# main.net
KiCad netlist of a schematic drawn in EAGLE
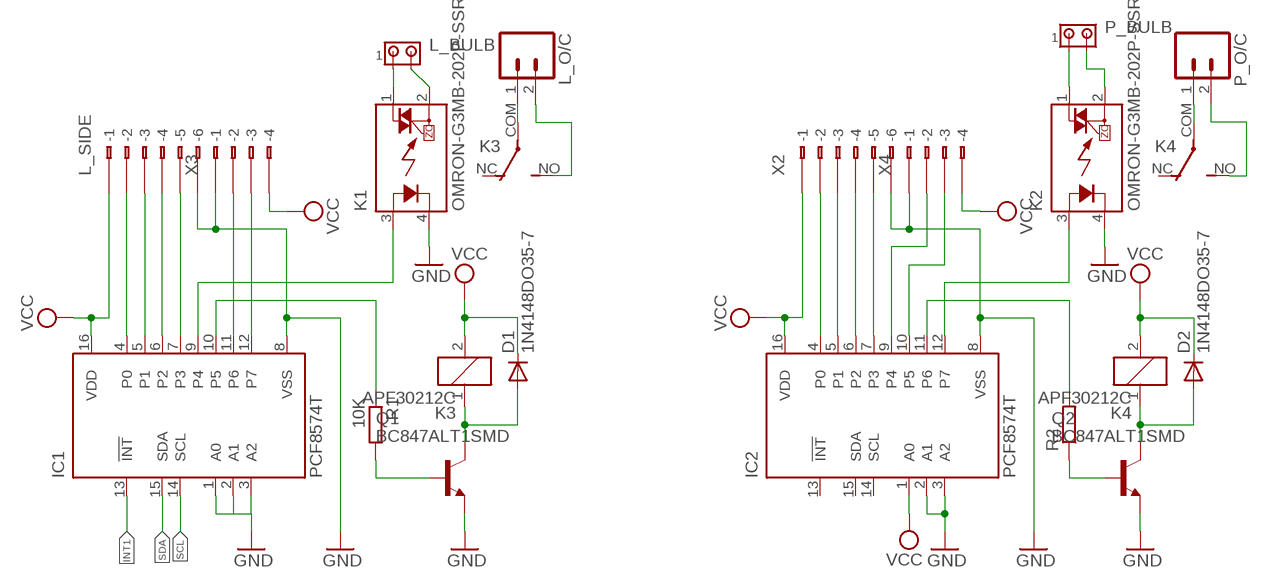
[diagram p0: schematic, sheet 1]

(export (version "E")
  (design (tool "Eeschema 10.0.6"))
  (components
    (comp (ref "D1")
      (value "1N4148DO35-7")
      (footprint "eagle-import:DO35-7")
      (libsource (lib "eagle-import") (part "1N4148DO35-7"))
    )
    (comp (ref "D2")
      (value "1N4148DO35-7")
      (footprint "eagle-import:DO35-7")
      (libsource (lib "eagle-import") (part "1N4148DO35-7"))
    )
    (comp (ref "IC1")
      (value "PCF8574T")
      (footprint "eagle-import:SO16W")
      (fields (field (name "MPN") "PCF8574T/3,512"))
      (libsource (lib "eagle-import") (part "PCF8574T"))
    )
    (comp (ref "IC2")
      (value "PCF8574T")
      (footprint "eagle-import:SO16W")
      (fields (field (name "MPN") "PCF8574T/3,512"))
      (libsource (lib "eagle-import") (part "PCF8574T"))
    )
    (comp (ref "K1")
      (value "OMRON-G3MB-202P-SSR")
      (footprint "eagle-import:OMRON-G3MB-202P-SSR")
      (libsource (lib "eagle-import") (part "OMRON-G3MB-202P-SSR"))
    )
    (comp (ref "K2")
      (value "OMRON-G3MB-202P-SSR")
      (footprint "eagle-import:OMRON-G3MB-202P-SSR")
      (libsource (lib "eagle-import") (part "OMRON-G3MB-202P-SSR"))
    )
    (comp (ref "K3")
      (value "APF30212C")
      (footprint "eagle-import:APF30212C")
      (libsource (lib "eagle-import") (part "APF30212C"))
    )
    (comp (ref "K4")
      (value "APF30212C")
      (footprint "eagle-import:APF30212C")
      (libsource (lib "eagle-import") (part "APF30212C"))
    )
    (comp (ref "L_BULB")
      (value "MTA02-156")
      (footprint "eagle-import:1X2MTA")
      (libsource (lib "eagle-import") (part "MTA02-156"))
    )
    (comp (ref "L_O/C")
      (value "M02")
      (footprint "eagle-import:02P")
      (libsource (lib "eagle-import") (part "M02"))
    )
    (comp (ref "L_SIDE")
      (value "233-106")
      (footprint "eagle-import:233-106")
      (libsource (lib "eagle-import") (part "233-106"))
    )
    (comp (ref "P_BULB")
      (value "MTA02-156")
      (footprint "eagle-import:1X2MTA")
      (libsource (lib "eagle-import") (part "MTA02-156"))
    )
    (comp (ref "P_O/C")
      (value "M02")
      (footprint "eagle-import:02P")
      (libsource (lib "eagle-import") (part "M02"))
    )
    (comp (ref "Q1")
      (value "BC847ALT1SMD")
      (footprint "eagle-import:SOT23")
      (libsource (lib "eagle-import") (part "BC847SMDALT1"))
    )
    (comp (ref "Q2")
      (value "BC847ALT1SMD")
      (footprint "eagle-import:SOT23")
      (libsource (lib "eagle-import") (part "BC847SMDALT1"))
    )
    (comp (ref "R1")
      (value "10K")
      (footprint "eagle-import:R0805W")
      (libsource (lib "eagle-import") (part "R-EU_R0805W"))
    )
    (comp (ref "R2")
      (value "R-EU_R0805W")
      (footprint "eagle-import:R0805W")
      (libsource (lib "eagle-import") (part "R-EU_R0805W"))
    )
    (comp (ref "X2")
      (value "233-106")
      (footprint "eagle-import:233-106")
      (libsource (lib "eagle-import") (part "233-106"))
    )
    (comp (ref "X3")
      (value "233-104")
      (footprint "eagle-import:233-104")
      (libsource (lib "eagle-import") (part "233-104"))
    )
    (comp (ref "X4")
      (value "233-104")
      (footprint "eagle-import:233-104")
      (libsource (lib "eagle-import") (part "233-104"))
    )
  )
  (nets
    (net (code "1") (name "GND") (class "Default")
      (node (ref "IC1") (pin "1") (pinfunction "A0_1") (pintype "input"))
      (node (ref "IC1") (pin "2") (pinfunction "A1_2") (pintype "input"))
      (node (ref "IC1") (pin "3") (pinfunction "A2_3") (pintype "input"))
      (node (ref "IC1") (pin "8") (pinfunction "VSS_8") (pintype "power_in"))
      (node (ref "IC2") (pin "2") (pinfunction "A1_2") (pintype "input"))
      (node (ref "IC2") (pin "3") (pinfunction "A2_3") (pintype "input"))
      (node (ref "IC2") (pin "8") (pinfunction "VSS_8") (pintype "power_in"))
      (node (ref "K1") (pin "4") (pinfunction "K_4") (pintype "passive"))
      (node (ref "K2") (pin "4") (pinfunction "K_4") (pintype "passive"))
      (node (ref "L_SIDE") (pin "B6") (pinfunction "B-6_B6") (pintype "passive"))
      (node (ref "Q1") (pin "2") (pinfunction "E_2") (pintype "passive"))
      (node (ref "Q2") (pin "2") (pinfunction "E_2") (pintype "passive"))
      (node (ref "X2") (pin "B6") (pinfunction "B-6_B6") (pintype "passive"))
      (node (ref "X3") (pin "B1") (pinfunction "B-1_B1") (pintype "passive"))
      (node (ref "X4") (pin "B1") (pinfunction "B-1_B1") (pintype "passive"))
    )
    (net (code "2") (name "INT1") (class "Default")
      (node (ref "IC1") (pin "13") (pinfunction "~{INT}_13") (pintype "output"))
    )
    (net (code "3") (name "Net-(IC1-P0)") (class "Default")
      (node (ref "IC1") (pin "4") (pinfunction "P0_4") (pintype "bidirectional"))
      (node (ref "L_SIDE") (pin "B2") (pinfunction "B-2_B2") (pintype "passive"))
    )
    (net (code "4") (name "Net-(IC1-P1)") (class "Default")
      (node (ref "IC1") (pin "5") (pinfunction "P1_5") (pintype "bidirectional"))
      (node (ref "L_SIDE") (pin "B3") (pinfunction "B-3_B3") (pintype "passive"))
    )
    (net (code "5") (name "Net-(IC1-P2)") (class "Default")
      (node (ref "IC1") (pin "6") (pinfunction "P2_6") (pintype "bidirectional"))
      (node (ref "L_SIDE") (pin "B4") (pinfunction "B-4_B4") (pintype "passive"))
    )
    (net (code "6") (name "Net-(IC1-P3)") (class "Default")
      (node (ref "IC1") (pin "7") (pinfunction "P3_7") (pintype "bidirectional"))
      (node (ref "L_SIDE") (pin "B5") (pinfunction "B-5_B5") (pintype "passive"))
    )
    (net (code "7") (name "Net-(IC1-P4)") (class "Default")
      (node (ref "IC1") (pin "9") (pinfunction "P4_9") (pintype "bidirectional"))
      (node (ref "K1") (pin "3") (pinfunction "A_3") (pintype "passive"))
    )
    (net (code "8") (name "Net-(IC1-P5)") (class "Default")
      (node (ref "IC1") (pin "10") (pinfunction "P5_10") (pintype "bidirectional"))
      (node (ref "R1") (pin "1") (pinfunction "1_1") (pintype "passive"))
    )
    (net (code "9") (name "Net-(IC1-P6)") (class "Default")
      (node (ref "IC1") (pin "11") (pinfunction "P6_11") (pintype "bidirectional"))
      (node (ref "X3") (pin "B2") (pinfunction "B-2_B2") (pintype "passive"))
    )
    (net (code "10") (name "Net-(IC1-P7)") (class "Default")
      (node (ref "IC1") (pin "12") (pinfunction "P7_12") (pintype "bidirectional"))
      (node (ref "X3") (pin "B3") (pinfunction "B-3_B3") (pintype "passive"))
    )
    (net (code "11") (name "Net-(IC2-P0)") (class "Default")
      (node (ref "IC2") (pin "4") (pinfunction "P0_4") (pintype "bidirectional"))
      (node (ref "X2") (pin "B2") (pinfunction "B-2_B2") (pintype "passive"))
    )
    (net (code "12") (name "Net-(IC2-P1)") (class "Default")
      (node (ref "IC2") (pin "5") (pinfunction "P1_5") (pintype "bidirectional"))
      (node (ref "X2") (pin "B3") (pinfunction "B-3_B3") (pintype "passive"))
    )
    (net (code "13") (name "Net-(IC2-P2)") (class "Default")
      (node (ref "IC2") (pin "6") (pinfunction "P2_6") (pintype "bidirectional"))
      (node (ref "X2") (pin "B4") (pinfunction "B-4_B4") (pintype "passive"))
    )
    (net (code "14") (name "Net-(IC2-P3)") (class "Default")
      (node (ref "IC2") (pin "7") (pinfunction "P3_7") (pintype "bidirectional"))
      (node (ref "X2") (pin "B5") (pinfunction "B-5_B5") (pintype "passive"))
    )
    (net (code "15") (name "Net-(IC2-P4)") (class "Default")
      (node (ref "IC2") (pin "9") (pinfunction "P4_9") (pintype "bidirectional"))
      (node (ref "X4") (pin "B2") (pinfunction "B-2_B2") (pintype "passive"))
    )
    (net (code "16") (name "Net-(IC2-P5)") (class "Default")
      (node (ref "IC2") (pin "10") (pinfunction "P5_10") (pintype "bidirectional"))
      (node (ref "X4") (pin "B3") (pinfunction "B-3_B3") (pintype "passive"))
    )
    (net (code "17") (name "Net-(IC2-P6)") (class "Default")
      (node (ref "IC2") (pin "11") (pinfunction "P6_11") (pintype "bidirectional"))
      (node (ref "R2") (pin "2") (pinfunction "2_2") (pintype "passive"))
    )
    (net (code "18") (name "Net-(IC2-P7)") (class "Default")
      (node (ref "IC2") (pin "12") (pinfunction "P7_12") (pintype "bidirectional"))
      (node (ref "K2") (pin "3") (pinfunction "A_3") (pintype "passive"))
    )
    (net (code "19") (name "Net-(K1-DS1)") (class "Default")
      (node (ref "K1") (pin "1") (pinfunction "DS1_1") (pintype "passive"))
      (node (ref "L_BULB") (pin "1") (pinfunction "1_1") (pintype "passive"))
    )
    (net (code "20") (name "Net-(K1-DS2)") (class "Default")
      (node (ref "K1") (pin "2") (pinfunction "DS2_2") (pintype "passive"))
      (node (ref "L_BULB") (pin "2") (pinfunction "2_2") (pintype "passive"))
    )
    (net (code "21") (name "Net-(K2-DS1)") (class "Default")
      (node (ref "K2") (pin "1") (pinfunction "DS1_1") (pintype "passive"))
      (node (ref "P_BULB") (pin "1") (pinfunction "1_1") (pintype "passive"))
    )
    (net (code "22") (name "Net-(K2-DS2)") (class "Default")
      (node (ref "K2") (pin "2") (pinfunction "DS2_2") (pintype "passive"))
      (node (ref "P_BULB") (pin "2") (pinfunction "2_2") (pintype "passive"))
    )
    (net (code "23") (name "Net-(K3B-P)") (class "Default")
      (node (ref "K3") (pin "COM") (pinfunction "P_COM") (pintype "passive"))
      (node (ref "L_O/C") (pin "1") (pinfunction "1_1") (pintype "passive"))
    )
    (net (code "24") (name "Net-(K3B-S)") (class "Default")
      (node (ref "K3") (pin "NO") (pinfunction "S_NO") (pintype "passive"))
      (node (ref "L_O/C") (pin "2") (pinfunction "2_2") (pintype "passive"))
    )
    (net (code "25") (name "Net-(K4B-P)") (class "Default")
      (node (ref "K4") (pin "COM") (pinfunction "P_COM") (pintype "passive"))
      (node (ref "P_O/C") (pin "1") (pinfunction "1_1") (pintype "passive"))
    )
    (net (code "26") (name "Net-(K4B-S)") (class "Default")
      (node (ref "K4") (pin "NO") (pinfunction "S_NO") (pintype "passive"))
      (node (ref "P_O/C") (pin "2") (pinfunction "2_2") (pintype "passive"))
    )
    (net (code "27") (name "Net-(Q1-B)") (class "Default")
      (node (ref "Q1") (pin "1") (pinfunction "B_1") (pintype "passive"))
      (node (ref "R1") (pin "2") (pinfunction "2_2") (pintype "passive"))
    )
    (net (code "28") (name "Net-(Q1-C)") (class "Default")
      (node (ref "D1") (pin "A") (pinfunction "A_A") (pintype "passive"))
      (node (ref "K3") (pin "1") (pinfunction "1_1") (pintype "passive"))
      (node (ref "Q1") (pin "3") (pinfunction "C_3") (pintype "passive"))
    )
    (net (code "29") (name "Net-(Q2-B)") (class "Default")
      (node (ref "Q2") (pin "1") (pinfunction "B_1") (pintype "passive"))
      (node (ref "R2") (pin "1") (pinfunction "1_1") (pintype "passive"))
    )
    (net (code "30") (name "Net-(Q2-C)") (class "Default")
      (node (ref "D2") (pin "A") (pinfunction "A_A") (pintype "passive"))
      (node (ref "K4") (pin "1") (pinfunction "1_1") (pintype "passive"))
      (node (ref "Q2") (pin "3") (pinfunction "C_3") (pintype "passive"))
    )
    (net (code "31") (name "SCL") (class "Default")
      (node (ref "IC1") (pin "14") (pinfunction "SCL_14") (pintype "input"))
    )
    (net (code "32") (name "SDA") (class "Default")
      (node (ref "IC1") (pin "15") (pinfunction "SDA_15") (pintype "bidirectional"))
    )
    (net (code "33") (name "VCC") (class "Default")
      (node (ref "D1") (pin "C") (pinfunction "C_C") (pintype "passive"))
      (node (ref "D2") (pin "C") (pinfunction "C_C") (pintype "passive"))
      (node (ref "IC1") (pin "16") (pinfunction "VDD_16") (pintype "power_in"))
      (node (ref "IC2") (pin "1") (pinfunction "A0_1") (pintype "input"))
      (node (ref "IC2") (pin "16") (pinfunction "VDD_16") (pintype "power_in"))
      (node (ref "K3") (pin "2") (pinfunction "2_2") (pintype "passive"))
      (node (ref "K4") (pin "2") (pinfunction "2_2") (pintype "passive"))
      (node (ref "L_SIDE") (pin "B1") (pinfunction "B-1_B1") (pintype "passive"))
      (node (ref "X2") (pin "B1") (pinfunction "B-1_B1") (pintype "passive"))
      (node (ref "X3") (pin "B4") (pinfunction "B-4_B4") (pintype "passive"))
      (node (ref "X4") (pin "B4") (pinfunction "B-4_B4") (pintype "passive"))
    )
    (net (code "34") (name "unconnected-(IC2-SCL-Pad14)") (class "Default")
      (node (ref "IC2") (pin "14") (pinfunction "SCL_14") (pintype "input"))
    )
    (net (code "35") (name "unconnected-(IC2-SDA-Pad15)") (class "Default")
      (node (ref "IC2") (pin "15") (pinfunction "SDA_15") (pintype "bidirectional"))
    )
    (net (code "36") (name "unconnected-(IC2-~{INT}-Pad13)") (class "Default")
      (node (ref "IC2") (pin "13") (pinfunction "~{INT}_13") (pintype "output"))
    )
    (net (code "37") (name "unconnected-(K3B-O-PadNC)") (class "Default")
      (node (ref "K3") (pin "NC") (pinfunction "O_NC") (pintype "passive"))
    )
    (net (code "38") (name "unconnected-(K4B-O-PadNC)") (class "Default")
      (node (ref "K4") (pin "NC") (pinfunction "O_NC") (pintype "passive"))
    )
    (net (code "39") (name "unconnected-(L_SIDE--1-PadA1)") (class "Default")
      (node (ref "L_SIDE") (pin "A1") (pinfunction "-1_A1") (pintype "passive"))
    )
    (net (code "40") (name "unconnected-(L_SIDE--2-PadA2)") (class "Default")
      (node (ref "L_SIDE") (pin "A2") (pinfunction "-2_A2") (pintype "passive"))
    )
    (net (code "41") (name "unconnected-(L_SIDE--3-PadA3)") (class "Default")
      (node (ref "L_SIDE") (pin "A3") (pinfunction "-3_A3") (pintype "passive"))
    )
    (net (code "42") (name "unconnected-(L_SIDE--4-PadA4)") (class "Default")
      (node (ref "L_SIDE") (pin "A4") (pinfunction "-4_A4") (pintype "passive"))
    )
    (net (code "43") (name "unconnected-(L_SIDE--5-PadA5)") (class "Default")
      (node (ref "L_SIDE") (pin "A5") (pinfunction "-5_A5") (pintype "passive"))
    )
    (net (code "44") (name "unconnected-(L_SIDE--6-PadA6)") (class "Default")
      (node (ref "L_SIDE") (pin "A6") (pinfunction "-6_A6") (pintype "passive"))
    )
    (net (code "45") (name "unconnected-(X2--1-PadA1)") (class "Default")
      (node (ref "X2") (pin "A1") (pinfunction "-1_A1") (pintype "passive"))
    )
    (net (code "46") (name "unconnected-(X2--2-PadA2)") (class "Default")
      (node (ref "X2") (pin "A2") (pinfunction "-2_A2") (pintype "passive"))
    )
    (net (code "47") (name "unconnected-(X2--3-PadA3)") (class "Default")
      (node (ref "X2") (pin "A3") (pinfunction "-3_A3") (pintype "passive"))
    )
    (net (code "48") (name "unconnected-(X2--4-PadA4)") (class "Default")
      (node (ref "X2") (pin "A4") (pinfunction "-4_A4") (pintype "passive"))
    )
    (net (code "49") (name "unconnected-(X2--5-PadA5)") (class "Default")
      (node (ref "X2") (pin "A5") (pinfunction "-5_A5") (pintype "passive"))
    )
    (net (code "50") (name "unconnected-(X2--6-PadA6)") (class "Default")
      (node (ref "X2") (pin "A6") (pinfunction "-6_A6") (pintype "passive"))
    )
    (net (code "51") (name "unconnected-(X3--1-PadA1)") (class "Default")
      (node (ref "X3") (pin "A1") (pinfunction "-1_A1") (pintype "passive"))
    )
    (net (code "52") (name "unconnected-(X3--2-PadA2)") (class "Default")
      (node (ref "X3") (pin "A2") (pinfunction "-2_A2") (pintype "passive"))
    )
    (net (code "53") (name "unconnected-(X3--3-PadA3)") (class "Default")
      (node (ref "X3") (pin "A3") (pinfunction "-3_A3") (pintype "passive"))
    )
    (net (code "54") (name "unconnected-(X3--4-PadA4)") (class "Default")
      (node (ref "X3") (pin "A4") (pinfunction "-4_A4") (pintype "passive"))
    )
    (net (code "55") (name "unconnected-(X4--1-PadA1)") (class "Default")
      (node (ref "X4") (pin "A1") (pinfunction "-1_A1") (pintype "passive"))
    )
    (net (code "56") (name "unconnected-(X4--2-PadA2)") (class "Default")
      (node (ref "X4") (pin "A2") (pinfunction "-2_A2") (pintype "passive"))
    )
    (net (code "57") (name "unconnected-(X4--3-PadA3)") (class "Default")
      (node (ref "X4") (pin "A3") (pinfunction "-3_A3") (pintype "passive"))
    )
    (net (code "58") (name "unconnected-(X4--4-PadA4)") (class "Default")
      (node (ref "X4") (pin "A4") (pinfunction "-4_A4") (pintype "passive"))
    )
  )
)
